# PIC32ETH_Main.net
KiCad netlist of a schematic drawn in Altium Designer
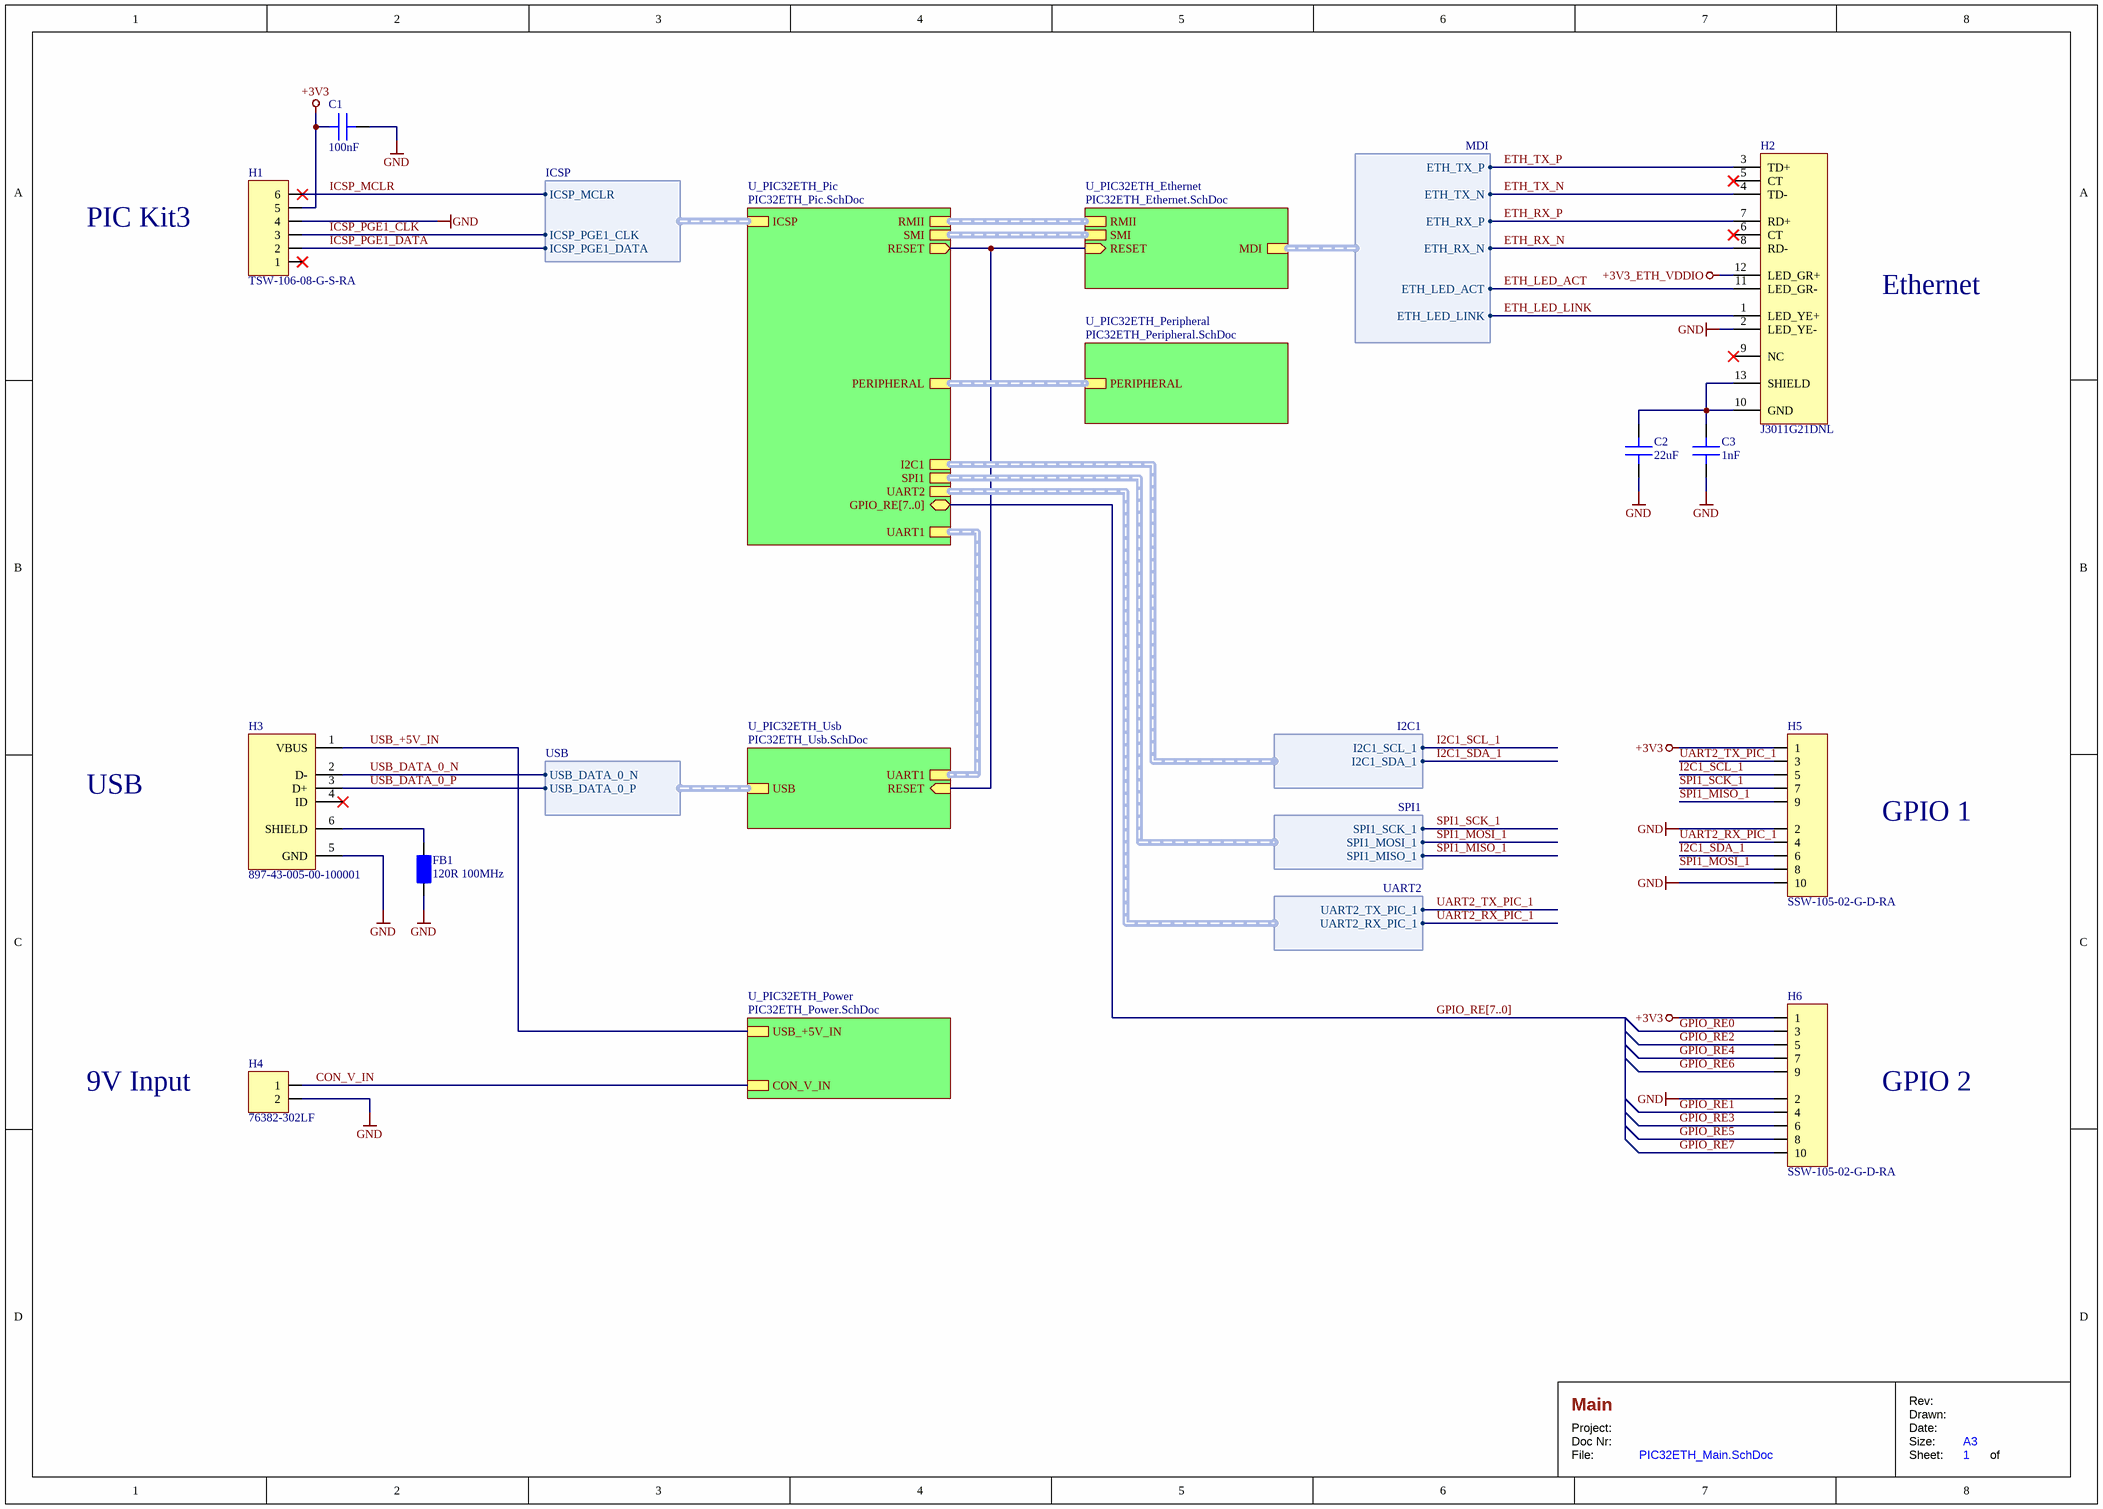
[diagram p0: PIC32ETH_Main.SchDoc]

(export (version "E")
  (design (tool "Eeschema 10.0.6"))
  (components
    (comp (ref "C1")
      (value "100nF")
      (footprint "C_CHIP2012N")
      (description "C CERAMIC 100nF 50V 10% 2012")
      (fields (field (name "MANUFACTURER") "Kemet") (field (name "PART NUMBER") "C0805C104K5RACTU"))
      (libsource (lib "C_Capacitor") (part "C_C0805C104K5RACTU"))
    )
    (comp (ref "C2")
      (value "22uF")
      (footprint "C_CHIP3216N")
      (description "C CERAMIC 22uF 10V 10% 3216")
      (fields (field (name "PART NUMBER") "C1206C226K8RAC7800") (field (name "MANUFACTURER") "Kemet"))
      (libsource (lib "C_Capacitor") (part "C_C1206C226K8RAC7800"))
    )
    (comp (ref "C3")
      (value "1nF")
      (footprint "C_CHIP2012N")
      (description "C CERAMIC 1nF 50V 10% 2012")
      (fields (field (name "MANUFACTURER") "Kemet") (field (name "PART NUMBER") "C0805C102K5RACTU"))
      (libsource (lib "C_Capacitor") (part "C_C0805C102K5RACTU"))
    )
    (comp (ref "FB1")
      (value "120R 100MHz")
      (footprint "FB_CHIP3216N")
      (description "FB 120R 100MHz 6A 3216")
      (fields
        (field (name "MANUFACTURER") "Murata Electronics")
        (field (name "PART NUMBER") "BLM31KN121SN1L")
      )
      (libsource (lib "FB_Ferrite_Bead") (part "FB_BLM31KN121SN1L"))
    )
    (comp (ref "H1")
      (value "TSW-106-08-G-S-RA")
      (footprint "H_TSW-106-08-G-S-RA")
      (description "H GENERAL HEADER 6POS 1ROW 2.54mm ANGLE THT")
      (fields (field (name "MANUFACTURER") "Samtec Inc.") (field (name "VOLTAGE") "550VAC, 770VDC"))
      (libsource (lib "H_Header") (part "H_TSW-106-08-G-S-RA"))
    )
    (comp (ref "H2")
      (value "J3011G21DNL")
      (footprint "H_J3011G21DNL")
      (description "H RJ45 SOCKET 1PORT ANGLE SMT")
      (fields (field (name "MANUFACTURER") "Pulse") (field (name "VOLTAGE") "n/a"))
      (libsource (lib "H_Header") (part "H_J3011G21DNL"))
    )
    (comp (ref "H3")
      (value "897-43-005-00-100001")
      (footprint "H_897-43-005-00-100001")
      (description "H USB SOCKET 1PORT B-MINI ANGLE SMT")
      (fields (field (name "MANUFACTURER") "Mill-Max Manufacturing Corp.") (field (name "VOLTAGE") "30VAC"))
      (libsource (lib "H_Header") (part "H_897-43-005-00-100001"))
    )
    (comp (ref "H4")
      (value "76382-302LF")
      (footprint "H_76382-302LF")
      (description "H GENERAL HEADER 2POS 1ROW 2.54mm ANGLE THT")
      (fields (field (name "MANUFACTURER") "Amphenol ICC") (field (name "VOLTAGE") "1000V"))
      (libsource (lib "H_Header") (part "H_76382-302LF"))
    )
    (comp (ref "H5")
      (value "SSW-105-02-G-D-RA")
      (footprint "H_SSW-105-02-G-D-RA")
      (description "H GENERAL SOCKET 10POS 2ROW 2.54mm ANGLE THT")
      (fields (field (name "MANUFACTURER") "Samtec Inc.") (field (name "VOLTAGE") "465VAC, 655VDC"))
      (libsource (lib "H_Header") (part "H_SSW-105-02-G-D-RA"))
    )
    (comp (ref "H6")
      (value "SSW-105-02-G-D-RA")
      (footprint "H_SSW-105-02-G-D-RA")
      (description "H GENERAL SOCKET 10POS 2ROW 2.54mm ANGLE THT")
      (fields (field (name "MANUFACTURER") "Samtec Inc.") (field (name "VOLTAGE") "465VAC, 655VDC"))
      (libsource (lib "H_Header") (part "H_SSW-105-02-G-D-RA"))
    )
  )
  (nets
    (net (code "7") (name "+3V3") (class "Default")
      (node (ref "C1") (pin "1") (pinfunction "1_1") (pintype "passive"))
      (node (ref "H1") (pin "5") (pinfunction "5_5") (pintype "passive"))
      (node (ref "H5") (pin "1") (pinfunction "1_1") (pintype "passive"))
      (node (ref "H6") (pin "1") (pinfunction "1_1") (pintype "passive"))
    )
    (net (code "8") (name "+3V3_ETH_VDDIO") (class "Default")
      (node (ref "H2") (pin "12") (pinfunction "LED_GR+_12") (pintype "passive"))
    )
    (net (code "9") (name "/CON_V_IN") (class "Default")
      (node (ref "H4") (pin "1") (pinfunction "1_1") (pintype "passive"))
    )
    (net (code "10") (name "/ETH_LED_ACT") (class "Default")
      (node (ref "H2") (pin "11") (pinfunction "LED_GR-_11") (pintype "passive"))
    )
    (net (code "11") (name "/ETH_LED_LINK") (class "Default")
      (node (ref "H2") (pin "1") (pinfunction "LED_YE+_1") (pintype "passive"))
    )
    (net (code "12") (name "/ETH_RX_N") (class "Default")
      (node (ref "H2") (pin "8") (pinfunction "RD-_8") (pintype "passive"))
    )
    (net (code "13") (name "/ETH_RX_P") (class "Default")
      (node (ref "H2") (pin "7") (pinfunction "RD+_7") (pintype "passive"))
    )
    (net (code "14") (name "/ETH_TX_N") (class "Default")
      (node (ref "H2") (pin "4") (pinfunction "TD-_4") (pintype "passive"))
    )
    (net (code "15") (name "/ETH_TX_P") (class "Default")
      (node (ref "H2") (pin "3") (pinfunction "TD+_3") (pintype "passive"))
    )
    (net (code "16") (name "/GPIO_RE0") (class "Default")
      (node (ref "H6") (pin "3") (pinfunction "3_3") (pintype "passive"))
    )
    (net (code "17") (name "/GPIO_RE1") (class "Default")
      (node (ref "H6") (pin "4") (pinfunction "4_4") (pintype "passive"))
    )
    (net (code "18") (name "/GPIO_RE2") (class "Default")
      (node (ref "H6") (pin "5") (pinfunction "5_5") (pintype "passive"))
    )
    (net (code "19") (name "/GPIO_RE3") (class "Default")
      (node (ref "H6") (pin "6") (pinfunction "6_6") (pintype "passive"))
    )
    (net (code "20") (name "/GPIO_RE4") (class "Default")
      (node (ref "H6") (pin "7") (pinfunction "7_7") (pintype "passive"))
    )
    (net (code "21") (name "/GPIO_RE5") (class "Default")
      (node (ref "H6") (pin "8") (pinfunction "8_8") (pintype "passive"))
    )
    (net (code "22") (name "/GPIO_RE6") (class "Default")
      (node (ref "H6") (pin "9") (pinfunction "9_9") (pintype "passive"))
    )
    (net (code "23") (name "/GPIO_RE7") (class "Default")
      (node (ref "H6") (pin "10") (pinfunction "10_10") (pintype "passive"))
    )
    (net (code "25") (name "/I2C1_SCL_1") (class "Default")
      (node (ref "H5") (pin "5") (pinfunction "5_5") (pintype "passive"))
    )
    (net (code "26") (name "/I2C1_SDA_1") (class "Default")
      (node (ref "H5") (pin "6") (pinfunction "6_6") (pintype "passive"))
    )
    (net (code "27") (name "/ICSP_MCLR") (class "Default")
      (node (ref "H1") (pin "6") (pinfunction "6_6") (pintype "passive+no_connect"))
    )
    (net (code "28") (name "/ICSP_PGE1_CLK") (class "Default")
      (node (ref "H1") (pin "3") (pinfunction "3_3") (pintype "passive"))
    )
    (net (code "29") (name "/ICSP_PGE1_DATA") (class "Default")
      (node (ref "H1") (pin "2") (pinfunction "2_2") (pintype "passive"))
    )
    (net (code "34") (name "/SPI1_MISO_1") (class "Default")
      (node (ref "H5") (pin "9") (pinfunction "9_9") (pintype "passive"))
    )
    (net (code "35") (name "/SPI1_MOSI_1") (class "Default")
      (node (ref "H5") (pin "8") (pinfunction "8_8") (pintype "passive"))
    )
    (net (code "36") (name "/SPI1_SCK_1") (class "Default")
      (node (ref "H5") (pin "7") (pinfunction "7_7") (pintype "passive"))
    )
    (net (code "38") (name "/UART2_RX_PIC_1") (class "Default")
      (node (ref "H5") (pin "4") (pinfunction "4_4") (pintype "passive"))
    )
    (net (code "39") (name "/UART2_TX_PIC_1") (class "Default")
      (node (ref "H5") (pin "3") (pinfunction "3_3") (pintype "passive"))
    )
    (net (code "40") (name "/USB_+5V_IN") (class "Default")
      (node (ref "H3") (pin "1") (pinfunction "VBUS_1") (pintype "passive"))
    )
    (net (code "41") (name "/USB_DATA_0_N") (class "Default")
      (node (ref "H3") (pin "2") (pinfunction "D-_2") (pintype "passive"))
    )
    (net (code "42") (name "/USB_DATA_0_P") (class "Default")
      (node (ref "H3") (pin "3") (pinfunction "D+_3") (pintype "passive"))
    )
    (net (code "49") (name "GND") (class "Default")
      (node (ref "C1") (pin "2") (pinfunction "2_2") (pintype "passive"))
      (node (ref "C2") (pin "1") (pinfunction "1_1") (pintype "passive"))
      (node (ref "C3") (pin "1") (pinfunction "1_1") (pintype "passive"))
      (node (ref "FB1") (pin "2") (pinfunction "2_2") (pintype "passive"))
      (node (ref "H1") (pin "4") (pinfunction "4_4") (pintype "passive"))
      (node (ref "H2") (pin "2") (pinfunction "LED_YE-_2") (pintype "passive"))
      (node (ref "H3") (pin "5") (pinfunction "GND_5") (pintype "passive"))
      (node (ref "H4") (pin "2") (pinfunction "2_2") (pintype "passive"))
      (node (ref "H5") (pin "10") (pinfunction "10_10") (pintype "passive"))
      (node (ref "H5") (pin "2") (pinfunction "2_2") (pintype "passive"))
      (node (ref "H6") (pin "2") (pinfunction "2_2") (pintype "passive"))
    )
    (net (code "50") (name "Net-(H2-GND)") (class "Default")
      (node (ref "C2") (pin "2") (pinfunction "2_2") (pintype "passive"))
      (node (ref "C3") (pin "2") (pinfunction "2_2") (pintype "passive"))
      (node (ref "H2") (pin "10") (pinfunction "GND_10") (pintype "passive"))
      (node (ref "H2") (pin "13") (pinfunction "SHIELD_13") (pintype "passive"))
    )
    (net (code "51") (name "Net-(H3-SHIELD)") (class "Default")
      (node (ref "FB1") (pin "1") (pinfunction "1_1") (pintype "passive"))
      (node (ref "H3") (pin "6") (pinfunction "SHIELD_6") (pintype "passive"))
    )
    (net (code "52") (name "unconnected-(H1-Pad1)") (class "Default")
      (node (ref "H1") (pin "1") (pinfunction "1_1") (pintype "passive+no_connect"))
    )
    (net (code "53") (name "unconnected-(H2-CT-Pad5)") (class "Default")
      (node (ref "H2") (pin "5") (pinfunction "CT_5") (pintype "passive+no_connect"))
    )
    (net (code "54") (name "unconnected-(H2-CT-Pad6)") (class "Default")
      (node (ref "H2") (pin "6") (pinfunction "CT_6") (pintype "passive+no_connect"))
    )
    (net (code "55") (name "unconnected-(H2-NC-Pad9)") (class "Default")
      (node (ref "H2") (pin "9") (pinfunction "NC_9") (pintype "passive+no_connect"))
    )
    (net (code "56") (name "unconnected-(H3-ID-Pad4)") (class "Default")
      (node (ref "H3") (pin "4") (pinfunction "ID_4") (pintype "passive+no_connect"))
    )
  )
)
